# USB.net
KiCad netlist of a schematic drawn in Altium Designer
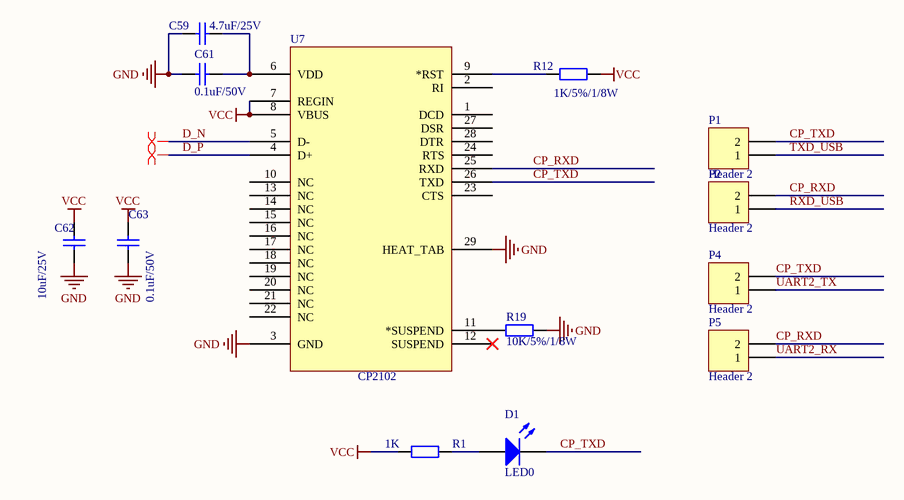
[diagram p0: USB.SchDoc]

(export (version "E")
  (design (tool "Eeschema 10.0.6"))
  (components
    (comp (ref "C59")
      (value "4.7uF/25V")
      (footprint "0603C")
      (description "Capacitor")
      (fields (field (name "PUBLISHER") "Altium Limited"))
      (libsource (lib "Miscellaneous Devices") (part "Cap"))
    )
    (comp (ref "C61")
      (value "0.1uF/50V")
      (footprint "0402C")
      (description "Capacitor")
      (fields (field (name "PUBLISHER") "Altium Limited"))
      (libsource (lib "Miscellaneous Devices") (part "Cap"))
    )
    (comp (ref "C62")
      (value "10uF/25V")
      (footprint "0603C")
      (description "Capacitor")
      (fields (field (name "PUBLISHER") "Altium Limited"))
      (libsource (lib "Miscellaneous Devices") (part "Cap"))
    )
    (comp (ref "C63")
      (value "0.1uF/50V")
      (footprint "0402C")
      (description "Capacitor")
      (fields (field (name "PUBLISHER") "Altium Limited"))
      (libsource (lib "Miscellaneous Devices") (part "Cap"))
    )
    (comp (ref "D1")
      (value "LED0")
      (footprint "0603LED")
      (description "Typical INFRARED GaAs LED")
      (fields (field (name "PUBLISHER") "Altium Limited"))
      (libsource (lib "Miscellaneous Devices") (part "LED0"))
    )
    (comp (ref "P1")
      (value "Header 2")
      (footprint "HDR1X2")
      (description "Header, 2-Pin")
      (fields (field (name "PUBLISHER") "Altium Limited"))
      (libsource (lib "Miscellaneous Connectors") (part "Header 2"))
    )
    (comp (ref "P2")
      (value "Header 2")
      (footprint "HDR1X2")
      (description "Header, 2-Pin")
      (fields (field (name "PUBLISHER") "Altium Limited"))
      (libsource (lib "Miscellaneous Connectors") (part "Header 2"))
    )
    (comp (ref "P4")
      (value "Header 2")
      (footprint "HDR1X2")
      (description "Header, 2-Pin")
      (fields (field (name "PUBLISHER") "Altium Limited"))
      (libsource (lib "Miscellaneous Connectors") (part "Header 2"))
    )
    (comp (ref "P5")
      (value "Header 2")
      (footprint "HDR1X2")
      (description "Header, 2-Pin")
      (fields (field (name "PUBLISHER") "Altium Limited"))
      (libsource (lib "Miscellaneous Connectors") (part "Header 2"))
    )
    (comp (ref "R1")
      (value "1K")
      (footprint "0402R")
      (description "Resistor SMD - IEC symbol version")
      (libsource (lib "SX1276_e266v02a") (part "Resistor"))
    )
    (comp (ref "R12")
      (value "1K/5%/1/8W")
      (footprint "0402R")
      (description "Resistor")
      (fields (field (name "PUBLISHER") "Altium Limited"))
      (libsource (lib "Miscellaneous Devices") (part "Res2"))
    )
    (comp (ref "R19")
      (value "10K/5%/1/8W")
      (footprint "0402R")
      (description "Resistor")
      (fields (field (name "PUBLISHER") "Altium Limited"))
      (libsource (lib "Miscellaneous Devices") (part "Res2"))
    )
    (comp (ref "U7")
      (value "CP2102")
      (footprint "QFN28N5X5-0p5P-L")
      (description "Imported")
      (libsource (lib "stm32") (part "CP2102"))
    )
  )
  (nets
    (net (code "1") (name "/CP_RXD") (class "Default")
      (node (ref "P2") (pin "2") (pinfunction "2_2") (pintype "passive"))
      (node (ref "P5") (pin "2") (pinfunction "2_2") (pintype "passive"))
      (node (ref "U7") (pin "25") (pinfunction "RXD_25") (pintype "passive"))
    )
    (net (code "2") (name "/CP_TXD") (class "Default")
      (node (ref "D1") (pin "2") (pinfunction "K_2") (pintype "passive"))
      (node (ref "P1") (pin "2") (pinfunction "2_2") (pintype "passive"))
      (node (ref "P4") (pin "2") (pinfunction "2_2") (pintype "passive"))
      (node (ref "U7") (pin "26") (pinfunction "TXD_26") (pintype "passive"))
    )
    (net (code "3") (name "/D_N") (class "Default")
      (node (ref "U7") (pin "5") (pinfunction "D-_5") (pintype "passive"))
    )
    (net (code "4") (name "/D_P") (class "Default")
      (node (ref "U7") (pin "4") (pinfunction "D+_4") (pintype "passive"))
    )
    (net (code "5") (name "/RXD_USB") (class "Default")
      (node (ref "P2") (pin "1") (pinfunction "1_1") (pintype "passive"))
    )
    (net (code "6") (name "/TXD_USB") (class "Default")
      (node (ref "P1") (pin "1") (pinfunction "1_1") (pintype "passive"))
    )
    (net (code "7") (name "/UART2_RX") (class "Default")
      (node (ref "P5") (pin "1") (pinfunction "1_1") (pintype "passive"))
    )
    (net (code "8") (name "/UART2_TX") (class "Default")
      (node (ref "P4") (pin "1") (pinfunction "1_1") (pintype "passive"))
    )
    (net (code "9") (name "GND") (class "Default")
      (node (ref "C59") (pin "1") (pinfunction "1_1") (pintype "passive"))
      (node (ref "C61") (pin "2") (pinfunction "2_2") (pintype "passive"))
      (node (ref "C62") (pin "2") (pinfunction "2_2") (pintype "passive"))
      (node (ref "C63") (pin "2") (pinfunction "2_2") (pintype "passive"))
      (node (ref "R19") (pin "1") (pinfunction "1_1") (pintype "passive"))
      (node (ref "U7") (pin "29") (pinfunction "HEAT_TAB_29") (pintype "passive"))
      (node (ref "U7") (pin "3") (pinfunction "GND_3") (pintype "passive"))
    )
    (net (code "10") (name "Net-(D1-A)") (class "Default")
      (node (ref "D1") (pin "1") (pinfunction "A_1") (pintype "passive"))
      (node (ref "R1") (pin "2") (pinfunction "2_2") (pintype "passive"))
    )
    (net (code "11") (name "Net-(U7-*RST)") (class "Default")
      (node (ref "R12") (pin "2") (pinfunction "2_2") (pintype "passive"))
      (node (ref "U7") (pin "9") (pinfunction "*RST_9") (pintype "passive"))
    )
    (net (code "12") (name "Net-(U7-*SUSPEND)") (class "Default")
      (node (ref "R19") (pin "2") (pinfunction "2_2") (pintype "passive"))
      (node (ref "U7") (pin "11") (pinfunction "*SUSPEND_11") (pintype "passive"))
    )
    (net (code "13") (name "Net-(U7-VDD)") (class "Default")
      (node (ref "C59") (pin "2") (pinfunction "2_2") (pintype "passive"))
      (node (ref "C61") (pin "1") (pinfunction "1_1") (pintype "passive"))
      (node (ref "U7") (pin "6") (pinfunction "VDD_6") (pintype "passive"))
    )
    (net (code "14") (name "VCC") (class "Default")
      (node (ref "C62") (pin "1") (pinfunction "1_1") (pintype "passive"))
      (node (ref "C63") (pin "1") (pinfunction "1_1") (pintype "passive"))
      (node (ref "R1") (pin "1") (pinfunction "1_1") (pintype "passive"))
      (node (ref "R12") (pin "1") (pinfunction "1_1") (pintype "passive"))
      (node (ref "U7") (pin "7") (pinfunction "REGIN_7") (pintype "passive"))
      (node (ref "U7") (pin "8") (pinfunction "VBUS_8") (pintype "passive"))
    )
    (net (code "15") (name "unconnected-(U7-CTS-Pad23)") (class "Default")
      (node (ref "U7") (pin "23") (pinfunction "CTS_23") (pintype "passive"))
    )
    (net (code "16") (name "unconnected-(U7-DCD-Pad1)") (class "Default")
      (node (ref "U7") (pin "1") (pinfunction "DCD_1") (pintype "passive"))
    )
    (net (code "17") (name "unconnected-(U7-DSR-Pad27)") (class "Default")
      (node (ref "U7") (pin "27") (pinfunction "DSR_27") (pintype "passive"))
    )
    (net (code "18") (name "unconnected-(U7-DTR-Pad28)") (class "Default")
      (node (ref "U7") (pin "28") (pinfunction "DTR_28") (pintype "passive"))
    )
    (net (code "19") (name "unconnected-(U7-NC-Pad10)") (class "Default")
      (node (ref "U7") (pin "10") (pinfunction "NC_10") (pintype "passive"))
    )
    (net (code "20") (name "unconnected-(U7-NC-Pad13)") (class "Default")
      (node (ref "U7") (pin "13") (pinfunction "NC_13") (pintype "passive"))
    )
    (net (code "21") (name "unconnected-(U7-NC-Pad14)") (class "Default")
      (node (ref "U7") (pin "14") (pinfunction "NC_14") (pintype "passive"))
    )
    (net (code "22") (name "unconnected-(U7-NC-Pad15)") (class "Default")
      (node (ref "U7") (pin "15") (pinfunction "NC_15") (pintype "passive"))
    )
    (net (code "23") (name "unconnected-(U7-NC-Pad16)") (class "Default")
      (node (ref "U7") (pin "16") (pinfunction "NC_16") (pintype "passive"))
    )
    (net (code "24") (name "unconnected-(U7-NC-Pad17)") (class "Default")
      (node (ref "U7") (pin "17") (pinfunction "NC_17") (pintype "passive"))
    )
    (net (code "25") (name "unconnected-(U7-NC-Pad18)") (class "Default")
      (node (ref "U7") (pin "18") (pinfunction "NC_18") (pintype "passive"))
    )
    (net (code "26") (name "unconnected-(U7-NC-Pad19)") (class "Default")
      (node (ref "U7") (pin "19") (pinfunction "NC_19") (pintype "passive"))
    )
    (net (code "27") (name "unconnected-(U7-NC-Pad20)") (class "Default")
      (node (ref "U7") (pin "20") (pinfunction "NC_20") (pintype "passive"))
    )
    (net (code "28") (name "unconnected-(U7-NC-Pad21)") (class "Default")
      (node (ref "U7") (pin "21") (pinfunction "NC_21") (pintype "passive"))
    )
    (net (code "29") (name "unconnected-(U7-NC-Pad22)") (class "Default")
      (node (ref "U7") (pin "22") (pinfunction "NC_22") (pintype "passive"))
    )
    (net (code "30") (name "unconnected-(U7-RI-Pad2)") (class "Default")
      (node (ref "U7") (pin "2") (pinfunction "RI_2") (pintype "passive"))
    )
    (net (code "31") (name "unconnected-(U7-RTS-Pad24)") (class "Default")
      (node (ref "U7") (pin "24") (pinfunction "RTS_24") (pintype "passive"))
    )
    (net (code "32") (name "unconnected-(U7-SUSPEND-Pad12)") (class "Default")
      (node (ref "U7") (pin "12") (pinfunction "SUSPEND_12") (pintype "passive+no_connect"))
    )
  )
)
